# Brickster_8884bt_Receiver.net
KiCad netlist of a schematic drawn in EAGLE
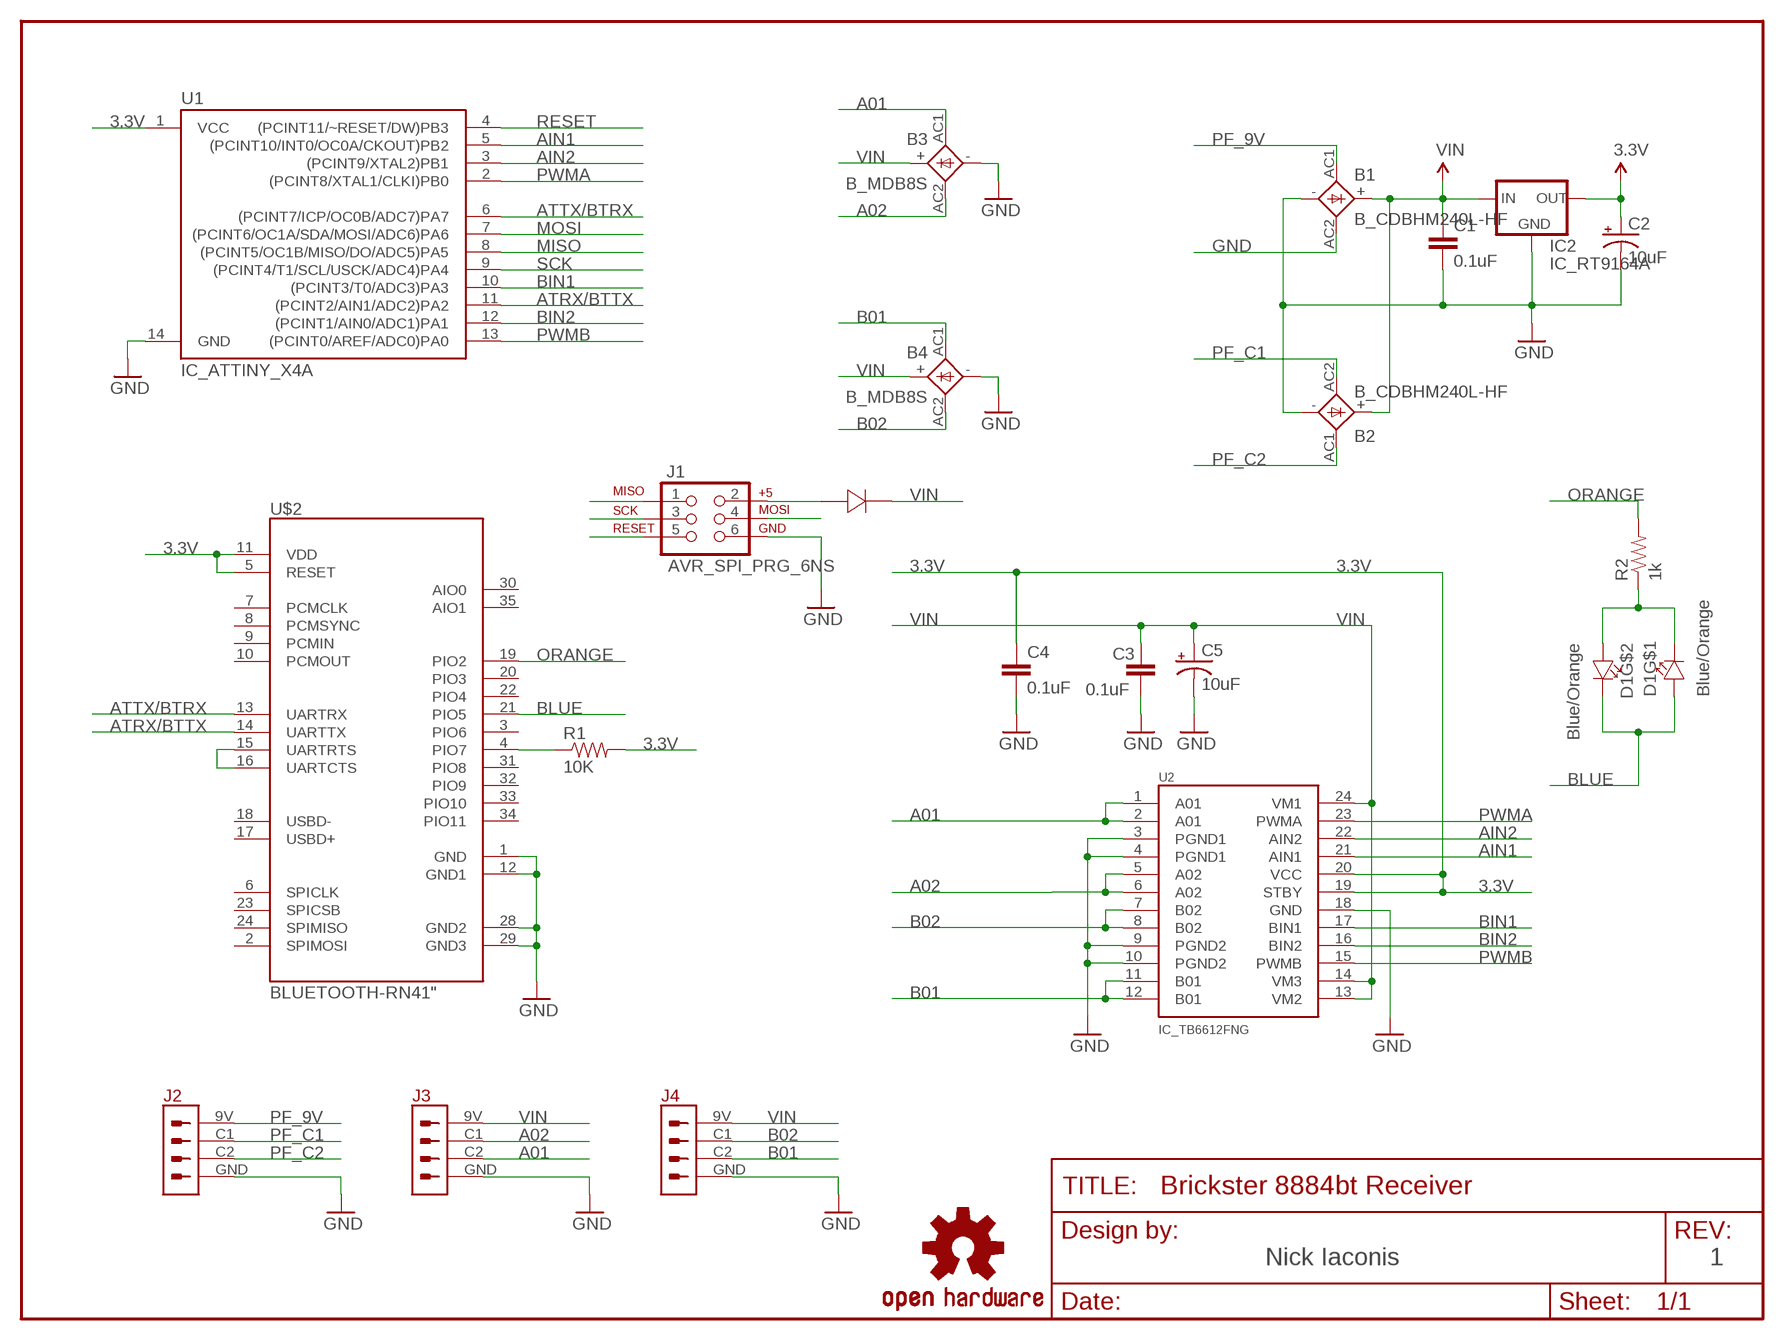
[diagram p0: schematic, sheet 1]

(export (version "E")
  (design (tool "Eeschema 10.0.6"))
  (components
    (comp (ref "B1")
      (value "B_CDBHM240L-HF")
      (footprint "eagle-import:MBS-2")
      (libsource (lib "eagle-import") (part "B_CDBHM240L-HF"))
    )
    (comp (ref "B2")
      (value "B_CDBHM240L-HF")
      (footprint "eagle-import:MBS-2")
      (libsource (lib "eagle-import") (part "B_CDBHM240L-HF"))
    )
    (comp (ref "B3")
      (value "B_MDB8S")
      (footprint "eagle-import:MICRO-DIP")
      (libsource (lib "eagle-import") (part "B_MDB8S"))
    )
    (comp (ref "B4")
      (value "B_MDB8S")
      (footprint "eagle-import:MICRO-DIP")
      (libsource (lib "eagle-import") (part "B_MDB8S"))
    )
    (comp (ref "C1")
      (value "0.1uF")
      (footprint "eagle-import:0402")
      (libsource (lib "eagle-import") (part "C"))
    )
    (comp (ref "C2")
      (value "10uF")
      (footprint "eagle-import:1206")
      (libsource (lib "eagle-import") (part "C_POL"))
    )
    (comp (ref "C3")
      (value "0.1uF")
      (footprint "eagle-import:0402")
      (libsource (lib "eagle-import") (part "C"))
    )
    (comp (ref "C4")
      (value "0.1uF")
      (footprint "eagle-import:0402")
      (libsource (lib "eagle-import") (part "C"))
    )
    (comp (ref "C5")
      (value "10uF")
      (footprint "eagle-import:1206")
      (libsource (lib "eagle-import") (part "C_POL"))
    )
    (comp (ref "D1")
      (value "Blue/Orange")
      (footprint "eagle-import:CHIP-LTST")
      (libsource (lib "eagle-import") (part "LED_LTST_C195TBKFKT"))
    )
    (comp (ref "D2") (value "D") (footprint "eagle-import:SOD80") (libsource (lib "eagle-import") (part "D")))
    (comp (ref "IC2")
      (value "IC_RT9164A")
      (footprint "eagle-import:SOT223")
      (libsource (lib "eagle-import") (part "IC_RT9164A"))
    )
    (comp (ref "J1")
      (value "AVR_SPI_PRG_6NS")
      (footprint "eagle-import:2X3-NS")
      (libsource (lib "eagle-import") (part "AVR_SPI_PRG_6NS"))
    )
    (comp (ref "J2")
      (value "CON_PF")
      (footprint "eagle-import:CON_PF")
      (libsource (lib "eagle-import") (part "CON_PF"))
    )
    (comp (ref "J3")
      (value "CON_PF")
      (footprint "eagle-import:CON_PF")
      (libsource (lib "eagle-import") (part "CON_PF"))
    )
    (comp (ref "J4")
      (value "CON_PF")
      (footprint "eagle-import:CON_PF")
      (libsource (lib "eagle-import") (part "CON_PF"))
    )
    (comp (ref "LOGO1")
      (value "OSHW-LOGOM")
      (footprint "eagle-import:OSHW-LOGO-M")
      (libsource (lib "eagle-import") (part "OSHW-LOGOM"))
    )
    (comp (ref "R1")
      (value "10K")
      (footprint "eagle-import:0402")
      (libsource (lib "eagle-import") (part "R"))
    )
    (comp (ref "R2") (value "1k") (footprint "eagle-import:0402") (libsource (lib "eagle-import") (part "R")))
    (comp (ref "U$2")
      (value "BLUETOOTH-RN41\"")
      (footprint "eagle-import:RN41")
      (libsource (lib "eagle-import") (part "BLUETOOTH-RN41{dblquote}"))
    )
    (comp (ref "U1")
      (value "IC_ATTINY_X4A")
      (footprint "eagle-import:14S1")
      (libsource (lib "eagle-import") (part "IC_ATTINY_X4A"))
    )
    (comp (ref "U2")
      (value "IC_TB6612FNG")
      (footprint "eagle-import:SSOP24")
      (libsource (lib "eagle-import") (part "IC_TB6612FNG"))
    )
  )
  (nets
    (net (code "1") (name "/A01") (class "Default")
      (node (ref "B3") (pin "AC1") (pinfunction "AC1_AC1") (pintype "passive"))
      (node (ref "J3") (pin "C2") (pinfunction "P$3_C2") (pintype "bidirectional"))
      (node (ref "U2") (pin "1") (pinfunction "A01_1") (pintype "bidirectional"))
      (node (ref "U2") (pin "2") (pinfunction "A01_2") (pintype "bidirectional"))
    )
    (net (code "2") (name "/A02") (class "Default")
      (node (ref "B3") (pin "AC2") (pinfunction "AC2_AC2") (pintype "passive"))
      (node (ref "J3") (pin "C1") (pinfunction "P$2_C1") (pintype "bidirectional"))
      (node (ref "U2") (pin "5") (pinfunction "A02_5") (pintype "bidirectional"))
      (node (ref "U2") (pin "6") (pinfunction "A02_6") (pintype "bidirectional"))
    )
    (net (code "3") (name "/AIN1") (class "Default")
      (node (ref "U1") (pin "5") (pinfunction "(PCINT10/INT0/OC0A/CKOUT)PB2_5") (pintype "bidirectional"))
      (node (ref "U2") (pin "21") (pinfunction "AIN1_21") (pintype "bidirectional"))
    )
    (net (code "4") (name "/AIN2") (class "Default")
      (node (ref "U1") (pin "3") (pinfunction "(PCINT9/XTAL2)PB1_3") (pintype "bidirectional"))
      (node (ref "U2") (pin "22") (pinfunction "AIN2_22") (pintype "bidirectional"))
    )
    (net (code "5") (name "/ATRX{slash}BTTX") (class "Default")
      (node (ref "U$2") (pin "14") (pinfunction "UARTTX_14") (pintype "bidirectional"))
      (node (ref "U1") (pin "11") (pinfunction "(PCINT2/AIN1/ADC2)PA2_11") (pintype "bidirectional"))
    )
    (net (code "6") (name "/ATTX{slash}BTRX") (class "Default")
      (node (ref "U$2") (pin "13") (pinfunction "UARTRX_13") (pintype "bidirectional"))
      (node (ref "U1") (pin "6") (pinfunction "(PCINT7/ICP/OC0B/ADC7)PA7_6") (pintype "bidirectional"))
    )
    (net (code "7") (name "/B01") (class "Default")
      (node (ref "B4") (pin "AC1") (pinfunction "AC1_AC1") (pintype "passive"))
      (node (ref "J4") (pin "C2") (pinfunction "P$3_C2") (pintype "bidirectional"))
      (node (ref "U2") (pin "11") (pinfunction "B01_11") (pintype "bidirectional"))
      (node (ref "U2") (pin "12") (pinfunction "B01_12") (pintype "bidirectional"))
    )
    (net (code "8") (name "/B02") (class "Default")
      (node (ref "B4") (pin "AC2") (pinfunction "AC2_AC2") (pintype "passive"))
      (node (ref "J4") (pin "C1") (pinfunction "P$2_C1") (pintype "bidirectional"))
      (node (ref "U2") (pin "7") (pinfunction "B02_7") (pintype "bidirectional"))
      (node (ref "U2") (pin "8") (pinfunction "B02_8") (pintype "bidirectional"))
    )
    (net (code "9") (name "/BIN1") (class "Default")
      (node (ref "U1") (pin "10") (pinfunction "(PCINT3/T0/ADC3)PA3_10") (pintype "bidirectional"))
      (node (ref "U2") (pin "17") (pinfunction "BIN1_17") (pintype "bidirectional"))
    )
    (net (code "10") (name "/BIN2") (class "Default")
      (node (ref "U1") (pin "12") (pinfunction "(PCINT1/AIN0/ADC1)PA1_12") (pintype "bidirectional"))
      (node (ref "U2") (pin "16") (pinfunction "BIN2_16") (pintype "bidirectional"))
    )
    (net (code "11") (name "/BLUE") (class "Default")
      (node (ref "D1") (pin "1") (pinfunction "P$1_1") (pintype "input"))
      (node (ref "D1") (pin "4") (pinfunction "P$2_4") (pintype "output"))
      (node (ref "U$2") (pin "21") (pinfunction "PIO5_21") (pintype "bidirectional"))
    )
    (net (code "12") (name "/MISO") (class "Default")
      (node (ref "J1") (pin "1") (pinfunction "1_1") (pintype "passive"))
      (node (ref "U1") (pin "8") (pinfunction "(PCINT5/OC1B/MISO/DO/ADC5)PA5_8") (pintype "bidirectional"))
    )
    (net (code "13") (name "/MOSI") (class "Default")
      (node (ref "J1") (pin "4") (pinfunction "4_4") (pintype "passive"))
      (node (ref "U1") (pin "7") (pinfunction "(PCINT6/OC1A/SDA/MOSI/ADC6)PA6_7") (pintype "bidirectional"))
    )
    (net (code "14") (name "/ORANGE") (class "Default")
      (node (ref "R2") (pin "2") (pinfunction "2_2") (pintype "passive"))
      (node (ref "U$2") (pin "19") (pinfunction "PIO2_19") (pintype "bidirectional"))
    )
    (net (code "15") (name "/PF_9V") (class "Default")
      (node (ref "B1") (pin "AC1") (pinfunction "AC1_AC1") (pintype "passive"))
      (node (ref "J2") (pin "9V") (pinfunction "P$1_9V") (pintype "bidirectional"))
    )
    (net (code "16") (name "/PF_C1") (class "Default")
      (node (ref "B2") (pin "AC2") (pinfunction "AC2_AC2") (pintype "passive"))
      (node (ref "J2") (pin "C1") (pinfunction "P$2_C1") (pintype "bidirectional"))
    )
    (net (code "17") (name "/PF_C2") (class "Default")
      (node (ref "B2") (pin "AC1") (pinfunction "AC1_AC1") (pintype "passive"))
      (node (ref "J2") (pin "C2") (pinfunction "P$3_C2") (pintype "bidirectional"))
    )
    (net (code "18") (name "/PWMA") (class "Default")
      (node (ref "U1") (pin "2") (pinfunction "(PCINT8/XTAL1/CLKI)PB0_2") (pintype "bidirectional"))
      (node (ref "U2") (pin "23") (pinfunction "PWMA_23") (pintype "bidirectional"))
    )
    (net (code "19") (name "/PWMB") (class "Default")
      (node (ref "U1") (pin "13") (pinfunction "(PCINT0/AREF/ADC0)PA0_13") (pintype "bidirectional"))
      (node (ref "U2") (pin "15") (pinfunction "PWMB_15") (pintype "bidirectional"))
    )
    (net (code "20") (name "/RESET") (class "Default")
      (node (ref "J1") (pin "5") (pinfunction "5_5") (pintype "passive"))
      (node (ref "U1") (pin "4") (pinfunction "(PCINT11/~{RESET/DW})PB3_4") (pintype "bidirectional"))
    )
    (net (code "21") (name "/SCK") (class "Default")
      (node (ref "J1") (pin "3") (pinfunction "3_3") (pintype "passive"))
      (node (ref "U1") (pin "9") (pinfunction "(PCINT4/T1/SCL/USCK/ADC4)PA4_9") (pintype "bidirectional"))
    )
    (net (code "22") (name "3.3V") (class "Default")
      (node (ref "C2") (pin "1") (pinfunction "+_1") (pintype "passive"))
      (node (ref "C4") (pin "1") (pinfunction "1_1") (pintype "passive"))
      (node (ref "IC2") (pin "2") (pinfunction "OUT_2") (pintype "output"))
      (node (ref "R1") (pin "2") (pinfunction "2_2") (pintype "passive"))
      (node (ref "U$2") (pin "11") (pinfunction "VDD_11") (pintype "bidirectional"))
      (node (ref "U$2") (pin "5") (pinfunction "RESET_5") (pintype "bidirectional"))
      (node (ref "U1") (pin "1") (pinfunction "VCC_1") (pintype "bidirectional"))
      (node (ref "U2") (pin "19") (pinfunction "STBY_19") (pintype "bidirectional"))
      (node (ref "U2") (pin "20") (pinfunction "VCC_20") (pintype "bidirectional"))
    )
    (net (code "23") (name "GND") (class "Default")
      (node (ref "B1") (pin "-") (pinfunction "-_-") (pintype "passive"))
      (node (ref "B1") (pin "AC2") (pinfunction "AC2_AC2") (pintype "passive"))
      (node (ref "B2") (pin "-") (pinfunction "-_-") (pintype "passive"))
      (node (ref "B3") (pin "-") (pinfunction "-_-") (pintype "passive"))
      (node (ref "B4") (pin "-") (pinfunction "-_-") (pintype "passive"))
      (node (ref "C1") (pin "2") (pinfunction "2_2") (pintype "passive"))
      (node (ref "C2") (pin "2") (pinfunction "-_2") (pintype "passive"))
      (node (ref "C3") (pin "2") (pinfunction "2_2") (pintype "passive"))
      (node (ref "C4") (pin "2") (pinfunction "2_2") (pintype "passive"))
      (node (ref "C5") (pin "2") (pinfunction "-_2") (pintype "passive"))
      (node (ref "IC2") (pin "1") (pinfunction "GND_1") (pintype "input"))
      (node (ref "J1") (pin "6") (pinfunction "6_6") (pintype "passive"))
      (node (ref "J2") (pin "GND") (pinfunction "P$4_GND") (pintype "bidirectional"))
      (node (ref "J3") (pin "GND") (pinfunction "P$4_GND") (pintype "bidirectional"))
      (node (ref "J4") (pin "GND") (pinfunction "P$4_GND") (pintype "bidirectional"))
      (node (ref "U$2") (pin "1") (pinfunction "GND_1") (pintype "bidirectional"))
      (node (ref "U$2") (pin "12") (pinfunction "GND1_12") (pintype "bidirectional"))
      (node (ref "U$2") (pin "28") (pinfunction "GND2_28") (pintype "bidirectional"))
      (node (ref "U$2") (pin "29") (pinfunction "GND3_29") (pintype "bidirectional"))
      (node (ref "U1") (pin "14") (pinfunction "GND_14") (pintype "bidirectional"))
      (node (ref "U2") (pin "10") (pinfunction "PGND2_10") (pintype "bidirectional"))
      (node (ref "U2") (pin "18") (pinfunction "GND_18") (pintype "bidirectional"))
      (node (ref "U2") (pin "3") (pinfunction "PGND1_3") (pintype "bidirectional"))
      (node (ref "U2") (pin "4") (pinfunction "PGND1_4") (pintype "bidirectional"))
      (node (ref "U2") (pin "9") (pinfunction "PGND2_9") (pintype "bidirectional"))
    )
    (net (code "24") (name "Net-(D1A-P$2)") (class "Default")
      (node (ref "D1") (pin "2") (pinfunction "P$1_2") (pintype "input"))
      (node (ref "D1") (pin "3") (pinfunction "P$2_3") (pintype "output"))
      (node (ref "R2") (pin "1") (pinfunction "1_1") (pintype "passive"))
    )
    (net (code "25") (name "Net-(D2-P$1)") (class "Default")
      (node (ref "D2") (pin "1") (pinfunction "P$1_1") (pintype "input"))
      (node (ref "J1") (pin "2") (pinfunction "2_2") (pintype "passive"))
    )
    (net (code "26") (name "Net-(U$2-PIO7)") (class "Default")
      (node (ref "R1") (pin "1") (pinfunction "1_1") (pintype "passive"))
      (node (ref "U$2") (pin "4") (pinfunction "PIO7_4") (pintype "bidirectional"))
    )
    (net (code "27") (name "Net-(U$2-UARTCTS)") (class "Default")
      (node (ref "U$2") (pin "15") (pinfunction "UARTRTS_15") (pintype "bidirectional"))
      (node (ref "U$2") (pin "16") (pinfunction "UARTCTS_16") (pintype "bidirectional"))
    )
    (net (code "28") (name "VIN") (class "Default")
      (node (ref "B1") (pin "+") (pinfunction "+_+") (pintype "passive"))
      (node (ref "B2") (pin "+") (pinfunction "+_+") (pintype "passive"))
      (node (ref "B3") (pin "+") (pinfunction "+_+") (pintype "passive"))
      (node (ref "B4") (pin "+") (pinfunction "+_+") (pintype "passive"))
      (node (ref "C1") (pin "1") (pinfunction "1_1") (pintype "passive"))
      (node (ref "C3") (pin "1") (pinfunction "1_1") (pintype "passive"))
      (node (ref "C5") (pin "1") (pinfunction "+_1") (pintype "passive"))
      (node (ref "D2") (pin "2") (pinfunction "P$2_2") (pintype "output"))
      (node (ref "IC2") (pin "3") (pinfunction "IN_3") (pintype "input"))
      (node (ref "J3") (pin "9V") (pinfunction "P$1_9V") (pintype "bidirectional"))
      (node (ref "J4") (pin "9V") (pinfunction "P$1_9V") (pintype "bidirectional"))
      (node (ref "U2") (pin "13") (pinfunction "VM2_13") (pintype "bidirectional"))
      (node (ref "U2") (pin "14") (pinfunction "VM3_14") (pintype "bidirectional"))
      (node (ref "U2") (pin "24") (pinfunction "VM1_24") (pintype "bidirectional"))
    )
    (net (code "29") (name "unconnected-(U$2-AIO0-Pad30)") (class "Default")
      (node (ref "U$2") (pin "30") (pinfunction "AIO0_30") (pintype "bidirectional"))
    )
    (net (code "30") (name "unconnected-(U$2-AIO1-Pad35)") (class "Default")
      (node (ref "U$2") (pin "35") (pinfunction "AIO1_35") (pintype "bidirectional"))
    )
    (net (code "31") (name "unconnected-(U$2-PCMCLK-Pad7)") (class "Default")
      (node (ref "U$2") (pin "7") (pinfunction "PCMCLK_7") (pintype "bidirectional"))
    )
    (net (code "32") (name "unconnected-(U$2-PCMIN-Pad9)") (class "Default")
      (node (ref "U$2") (pin "9") (pinfunction "PCMIN_9") (pintype "bidirectional"))
    )
    (net (code "33") (name "unconnected-(U$2-PCMOUT-Pad10)") (class "Default")
      (node (ref "U$2") (pin "10") (pinfunction "PCMOUT_10") (pintype "bidirectional"))
    )
    (net (code "34") (name "unconnected-(U$2-PCMSYNC-Pad8)") (class "Default")
      (node (ref "U$2") (pin "8") (pinfunction "PCMSYNC_8") (pintype "bidirectional"))
    )
    (net (code "35") (name "unconnected-(U$2-PIO3-Pad20)") (class "Default")
      (node (ref "U$2") (pin "20") (pinfunction "PIO3_20") (pintype "bidirectional"))
    )
    (net (code "36") (name "unconnected-(U$2-PIO4-Pad22)") (class "Default")
      (node (ref "U$2") (pin "22") (pinfunction "PIO4_22") (pintype "bidirectional"))
    )
    (net (code "37") (name "unconnected-(U$2-PIO6-Pad3)") (class "Default")
      (node (ref "U$2") (pin "3") (pinfunction "PIO6_3") (pintype "bidirectional"))
    )
    (net (code "38") (name "unconnected-(U$2-PIO8-Pad31)") (class "Default")
      (node (ref "U$2") (pin "31") (pinfunction "PIO8_31") (pintype "bidirectional"))
    )
    (net (code "39") (name "unconnected-(U$2-PIO9-Pad32)") (class "Default")
      (node (ref "U$2") (pin "32") (pinfunction "PIO9_32") (pintype "bidirectional"))
    )
    (net (code "40") (name "unconnected-(U$2-PIO10-Pad33)") (class "Default")
      (node (ref "U$2") (pin "33") (pinfunction "PIO10_33") (pintype "bidirectional"))
    )
    (net (code "41") (name "unconnected-(U$2-PIO11-Pad34)") (class "Default")
      (node (ref "U$2") (pin "34") (pinfunction "PIO11_34") (pintype "bidirectional"))
    )
    (net (code "42") (name "unconnected-(U$2-SPICLK-Pad6)") (class "Default")
      (node (ref "U$2") (pin "6") (pinfunction "SPICLK_6") (pintype "bidirectional"))
    )
    (net (code "43") (name "unconnected-(U$2-SPICSB-Pad23)") (class "Default")
      (node (ref "U$2") (pin "23") (pinfunction "SPICSB_23") (pintype "bidirectional"))
    )
    (net (code "44") (name "unconnected-(U$2-SPIMISO-Pad24)") (class "Default")
      (node (ref "U$2") (pin "24") (pinfunction "SPIMISO_24") (pintype "bidirectional"))
    )
    (net (code "45") (name "unconnected-(U$2-SPIMOSI-Pad2)") (class "Default")
      (node (ref "U$2") (pin "2") (pinfunction "SPIMOSI_2") (pintype "bidirectional"))
    )
    (net (code "46") (name "unconnected-(U$2-USBD+-Pad17)") (class "Default")
      (node (ref "U$2") (pin "17") (pinfunction "USBD+_17") (pintype "bidirectional"))
    )
    (net (code "47") (name "unconnected-(U$2-USBD--Pad18)") (class "Default")
      (node (ref "U$2") (pin "18") (pinfunction "USBD-_18") (pintype "bidirectional"))
    )
  )
)
